# QuadF32.net
KiCad netlist of a schematic drawn in EAGLE
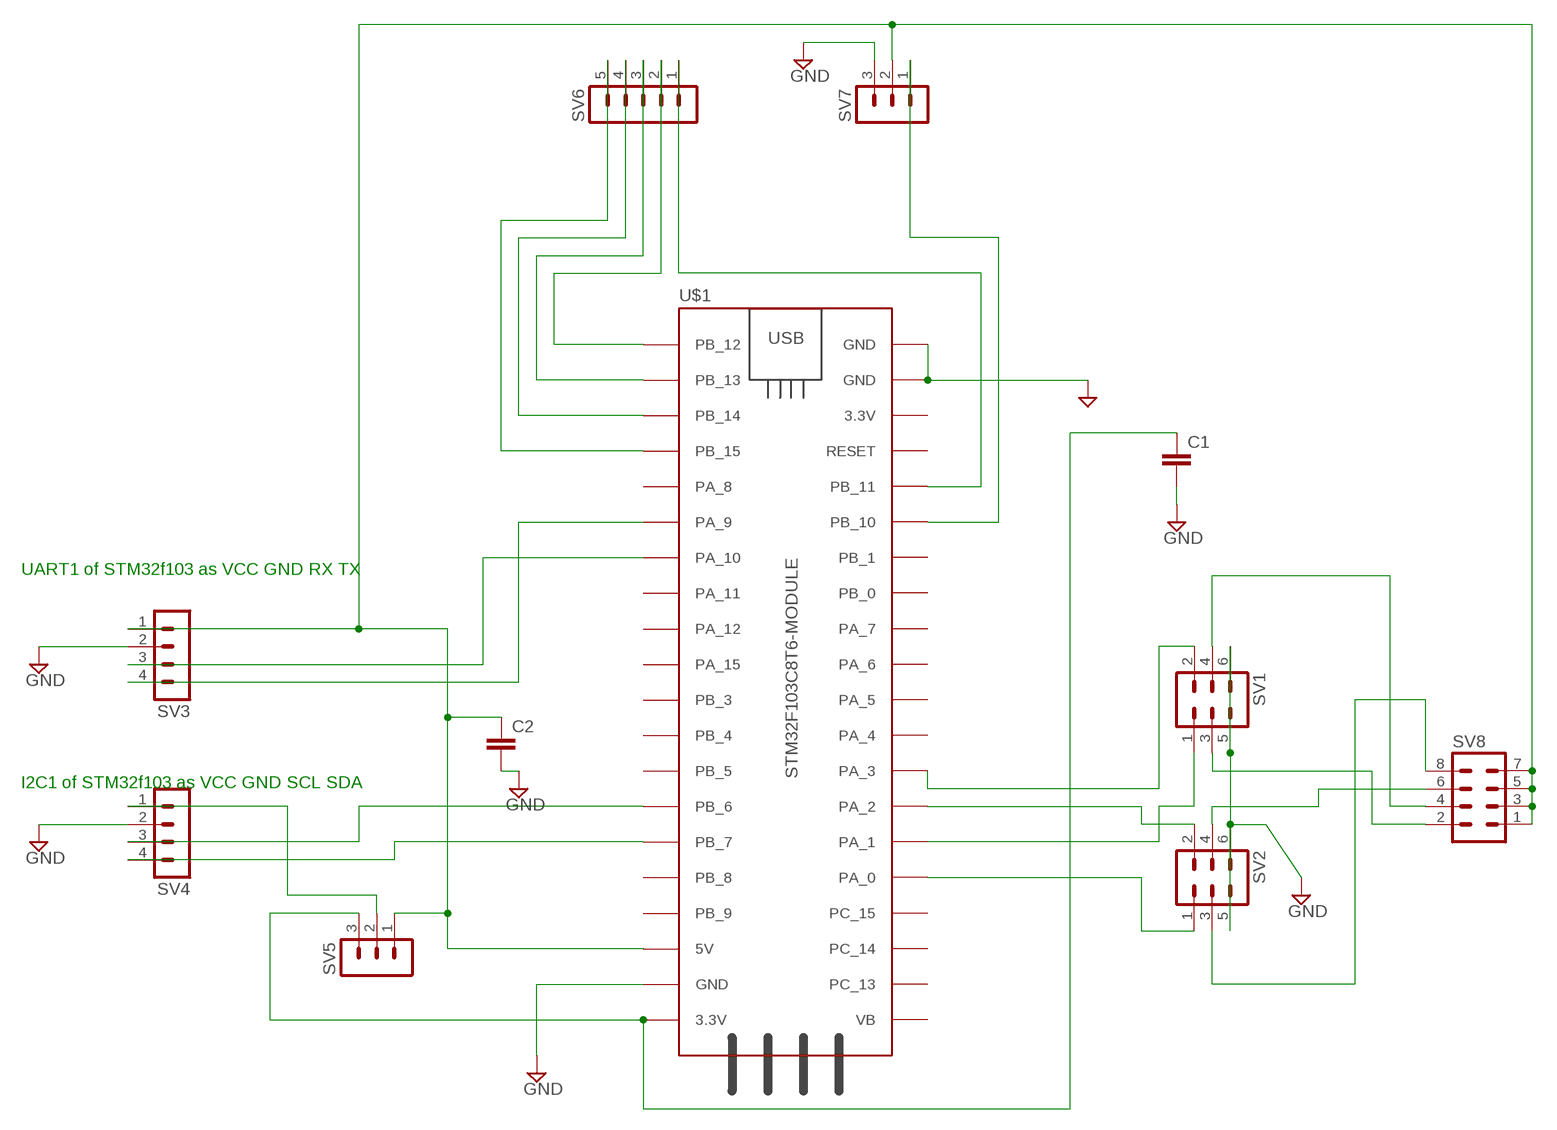
[diagram p0: schematic, sheet 1]

(export (version "E")
  (design (tool "Eeschema 10.0.6"))
  (components
    (comp (ref "C1")
      (value "C5/2.5")
      (footprint "eagle-import:C5B2.5")
      (libsource (lib "eagle-import") (part "C5/2.5"))
    )
    (comp (ref "C2")
      (value "C5/2.5")
      (footprint "eagle-import:C5B2.5")
      (libsource (lib "eagle-import") (part "C5/2.5"))
    )
    (comp (ref "SV1")
      (value "MA03-2")
      (footprint "eagle-import:MA03-2")
      (libsource (lib "eagle-import") (part "MA03-2"))
    )
    (comp (ref "SV2")
      (value "MA03-2")
      (footprint "eagle-import:MA03-2")
      (libsource (lib "eagle-import") (part "MA03-2"))
    )
    (comp (ref "SV3")
      (value "MA04-1")
      (footprint "eagle-import:MA04-1")
      (libsource (lib "eagle-import") (part "MA04-1"))
    )
    (comp (ref "SV4")
      (value "MA04-1")
      (footprint "eagle-import:MA04-1")
      (libsource (lib "eagle-import") (part "MA04-1"))
    )
    (comp (ref "SV5")
      (value "MA03-1")
      (footprint "eagle-import:MA03-1")
      (libsource (lib "eagle-import") (part "MA03-1"))
    )
    (comp (ref "SV6")
      (value "MA05-1")
      (footprint "eagle-import:MA05-1")
      (libsource (lib "eagle-import") (part "MA05-1"))
    )
    (comp (ref "SV7")
      (value "MA03-1")
      (footprint "eagle-import:MA03-1")
      (libsource (lib "eagle-import") (part "MA03-1"))
    )
    (comp (ref "SV8")
      (value "MA04-2")
      (footprint "eagle-import:MA04-2")
      (libsource (lib "eagle-import") (part "MA04-2"))
    )
    (comp (ref "U$1")
      (value "STM32F103C8T6-MODULE")
      (footprint "eagle-import:STM32F103C8T6-MODULE")
      (libsource (lib "eagle-import") (part "STM32F103C8T6-MODULE"))
    )
  )
  (nets
    (net (code "1") (name "GND") (class "Default")
      (node (ref "C1") (pin "2") (pinfunction "2_2") (pintype "passive"))
      (node (ref "C2") (pin "2") (pinfunction "2_2") (pintype "passive"))
      (node (ref "SV1") (pin "5") (pinfunction "5_5") (pintype "passive"))
      (node (ref "SV1") (pin "6") (pinfunction "6_6") (pintype "passive"))
      (node (ref "SV2") (pin "5") (pinfunction "5_5") (pintype "passive"))
      (node (ref "SV2") (pin "6") (pinfunction "6_6") (pintype "passive"))
      (node (ref "SV3") (pin "2") (pinfunction "2_2") (pintype "passive"))
      (node (ref "SV4") (pin "2") (pinfunction "2_2") (pintype "passive"))
      (node (ref "SV7") (pin "3") (pinfunction "3_3") (pintype "passive"))
      (node (ref "U$1") (pin "GND_1") (pinfunction "GND_GND_1") (pintype "bidirectional"))
      (node (ref "U$1") (pin "GND_2") (pinfunction "GND_GND_2") (pintype "bidirectional"))
      (node (ref "U$1") (pin "GND_3") (pinfunction "GND_GND_3") (pintype "power_in"))
    )
    (net (code "2") (name "Net-(C1-Pad1)") (class "Default")
      (node (ref "C1") (pin "1") (pinfunction "1_1") (pintype "passive"))
      (node (ref "SV5") (pin "3") (pinfunction "3_3") (pintype "passive"))
      (node (ref "U$1") (pin "3.3V_1") (pinfunction "3.3V_3.3V_1") (pintype "bidirectional"))
    )
    (net (code "3") (name "Net-(C2-Pad1)") (class "Default")
      (node (ref "C2") (pin "1") (pinfunction "1_1") (pintype "passive"))
      (node (ref "SV3") (pin "1") (pinfunction "1_1") (pintype "passive"))
      (node (ref "SV5") (pin "1") (pinfunction "1_1") (pintype "passive"))
      (node (ref "SV7") (pin "2") (pinfunction "2_2") (pintype "passive"))
      (node (ref "SV8") (pin "1") (pinfunction "1_1") (pintype "passive"))
      (node (ref "SV8") (pin "3") (pinfunction "3_3") (pintype "passive"))
      (node (ref "SV8") (pin "5") (pinfunction "5_5") (pintype "passive"))
      (node (ref "SV8") (pin "7") (pinfunction "7_7") (pintype "passive"))
      (node (ref "U$1") (pin "5V") (pinfunction "5V_5V") (pintype "bidirectional"))
    )
    (net (code "4") (name "Net-(SV1-Pad1)") (class "Default")
      (node (ref "SV1") (pin "1") (pinfunction "1_1") (pintype "passive"))
      (node (ref "U$1") (pin "PA_1") (pinfunction "PA_1_PA_1") (pintype "bidirectional"))
    )
    (net (code "5") (name "Net-(SV1-Pad2)") (class "Default")
      (node (ref "SV1") (pin "2") (pinfunction "2_2") (pintype "passive"))
      (node (ref "U$1") (pin "PA_3") (pinfunction "PA_3_PA_3") (pintype "bidirectional"))
    )
    (net (code "6") (name "Net-(SV1-Pad3)") (class "Default")
      (node (ref "SV1") (pin "3") (pinfunction "3_3") (pintype "passive"))
      (node (ref "SV8") (pin "2") (pinfunction "2_2") (pintype "passive"))
    )
    (net (code "7") (name "Net-(SV1-Pad4)") (class "Default")
      (node (ref "SV1") (pin "4") (pinfunction "4_4") (pintype "passive"))
      (node (ref "SV8") (pin "4") (pinfunction "4_4") (pintype "passive"))
    )
    (net (code "8") (name "Net-(SV2-Pad1)") (class "Default")
      (node (ref "SV2") (pin "1") (pinfunction "1_1") (pintype "passive"))
      (node (ref "U$1") (pin "PA_0") (pinfunction "PA_0_PA_0") (pintype "bidirectional"))
    )
    (net (code "9") (name "Net-(SV2-Pad2)") (class "Default")
      (node (ref "SV2") (pin "2") (pinfunction "2_2") (pintype "passive"))
      (node (ref "U$1") (pin "PA_2") (pinfunction "PA_2_PA_2") (pintype "bidirectional"))
    )
    (net (code "10") (name "Net-(SV2-Pad3)") (class "Default")
      (node (ref "SV2") (pin "3") (pinfunction "3_3") (pintype "passive"))
      (node (ref "SV8") (pin "8") (pinfunction "8_8") (pintype "passive"))
    )
    (net (code "11") (name "Net-(SV2-Pad4)") (class "Default")
      (node (ref "SV2") (pin "4") (pinfunction "4_4") (pintype "passive"))
      (node (ref "SV8") (pin "6") (pinfunction "6_6") (pintype "passive"))
    )
    (net (code "12") (name "Net-(SV3-Pad3)") (class "Default")
      (node (ref "SV3") (pin "3") (pinfunction "3_3") (pintype "passive"))
      (node (ref "U$1") (pin "PA_10") (pinfunction "PA_10_PA_10") (pintype "bidirectional"))
    )
    (net (code "13") (name "Net-(SV3-Pad4)") (class "Default")
      (node (ref "SV3") (pin "4") (pinfunction "4_4") (pintype "passive"))
      (node (ref "U$1") (pin "PA_9") (pinfunction "PA_9_PA_9") (pintype "bidirectional"))
    )
    (net (code "14") (name "Net-(SV4-Pad1)") (class "Default")
      (node (ref "SV4") (pin "1") (pinfunction "1_1") (pintype "passive"))
      (node (ref "SV5") (pin "2") (pinfunction "2_2") (pintype "passive"))
    )
    (net (code "15") (name "Net-(SV4-Pad3)") (class "Default")
      (node (ref "SV4") (pin "3") (pinfunction "3_3") (pintype "passive"))
      (node (ref "U$1") (pin "PB_6") (pinfunction "PB_6_PB_6") (pintype "bidirectional"))
    )
    (net (code "16") (name "Net-(SV4-Pad4)") (class "Default")
      (node (ref "SV4") (pin "4") (pinfunction "4_4") (pintype "passive"))
      (node (ref "U$1") (pin "PB_7") (pinfunction "PB_7_PB_7") (pintype "bidirectional"))
    )
    (net (code "17") (name "Net-(SV6-Pad1)") (class "Default")
      (node (ref "SV6") (pin "1") (pinfunction "1_1") (pintype "passive"))
      (node (ref "U$1") (pin "PB_11") (pinfunction "PB_11_PB_11") (pintype "bidirectional"))
    )
    (net (code "18") (name "Net-(SV6-Pad2)") (class "Default")
      (node (ref "SV6") (pin "2") (pinfunction "2_2") (pintype "passive"))
      (node (ref "U$1") (pin "PB_12") (pinfunction "PB_12_PB_12") (pintype "bidirectional"))
    )
    (net (code "19") (name "Net-(SV6-Pad3)") (class "Default")
      (node (ref "SV6") (pin "3") (pinfunction "3_3") (pintype "passive"))
      (node (ref "U$1") (pin "PB_13") (pinfunction "PB_13_PB_13") (pintype "bidirectional"))
    )
    (net (code "20") (name "Net-(SV6-Pad4)") (class "Default")
      (node (ref "SV6") (pin "4") (pinfunction "4_4") (pintype "passive"))
      (node (ref "U$1") (pin "PB_14") (pinfunction "PB_14_PB_14") (pintype "bidirectional"))
    )
    (net (code "21") (name "Net-(SV6-Pad5)") (class "Default")
      (node (ref "SV6") (pin "5") (pinfunction "5_5") (pintype "passive"))
      (node (ref "U$1") (pin "PB_15") (pinfunction "PB_15_PB_15") (pintype "bidirectional"))
    )
    (net (code "22") (name "Net-(SV7-Pad1)") (class "Default")
      (node (ref "SV7") (pin "1") (pinfunction "1_1") (pintype "passive"))
      (node (ref "U$1") (pin "PB_10") (pinfunction "PB_10_PB_10") (pintype "bidirectional"))
    )
    (net (code "23") (name "unconnected-(U$1-3.3V-Pad3.3V_2)") (class "Default")
      (node (ref "U$1") (pin "3.3V_2") (pinfunction "3.3V_3.3V_2") (pintype "bidirectional"))
    )
    (net (code "24") (name "unconnected-(U$1-PadPA_4)") (class "Default")
      (node (ref "U$1") (pin "PA_4") (pinfunction "PA_4_PA_4") (pintype "bidirectional"))
    )
    (net (code "25") (name "unconnected-(U$1-PadPA_5)") (class "Default")
      (node (ref "U$1") (pin "PA_5") (pinfunction "PA_5_PA_5") (pintype "bidirectional"))
    )
    (net (code "26") (name "unconnected-(U$1-PadPA_6)") (class "Default")
      (node (ref "U$1") (pin "PA_6") (pinfunction "PA_6_PA_6") (pintype "bidirectional"))
    )
    (net (code "27") (name "unconnected-(U$1-PadPA_7)") (class "Default")
      (node (ref "U$1") (pin "PA_7") (pinfunction "PA_7_PA_7") (pintype "bidirectional"))
    )
    (net (code "28") (name "unconnected-(U$1-PadPA_8)") (class "Default")
      (node (ref "U$1") (pin "PA_8") (pinfunction "PA_8_PA_8") (pintype "bidirectional"))
    )
    (net (code "29") (name "unconnected-(U$1-PadPA_11)") (class "Default")
      (node (ref "U$1") (pin "PA_11") (pinfunction "PA_11_PA_11") (pintype "bidirectional"))
    )
    (net (code "30") (name "unconnected-(U$1-PadPA_12)") (class "Default")
      (node (ref "U$1") (pin "PA_12") (pinfunction "PA_12_PA_12") (pintype "bidirectional"))
    )
    (net (code "31") (name "unconnected-(U$1-PadPA_15)") (class "Default")
      (node (ref "U$1") (pin "PA_15") (pinfunction "PA_15_PA_15") (pintype "bidirectional"))
    )
    (net (code "32") (name "unconnected-(U$1-PadPB_0)") (class "Default")
      (node (ref "U$1") (pin "PB_0") (pinfunction "PB_0_PB_0") (pintype "bidirectional"))
    )
    (net (code "33") (name "unconnected-(U$1-PadPB_1)") (class "Default")
      (node (ref "U$1") (pin "PB_1") (pinfunction "PB_1_PB_1") (pintype "bidirectional"))
    )
    (net (code "34") (name "unconnected-(U$1-PadPB_3)") (class "Default")
      (node (ref "U$1") (pin "PB_3") (pinfunction "PB_3_PB_3") (pintype "bidirectional"))
    )
    (net (code "35") (name "unconnected-(U$1-PadPB_4)") (class "Default")
      (node (ref "U$1") (pin "PB_4") (pinfunction "PB_4_PB_4") (pintype "bidirectional"))
    )
    (net (code "36") (name "unconnected-(U$1-PadPB_5)") (class "Default")
      (node (ref "U$1") (pin "PB_5") (pinfunction "PB_5_PB_5") (pintype "bidirectional"))
    )
    (net (code "37") (name "unconnected-(U$1-PadPB_8)") (class "Default")
      (node (ref "U$1") (pin "PB_8") (pinfunction "PB_8_PB_8") (pintype "bidirectional"))
    )
    (net (code "38") (name "unconnected-(U$1-PadPB_9)") (class "Default")
      (node (ref "U$1") (pin "PB_9") (pinfunction "PB_9_PB_9") (pintype "bidirectional"))
    )
    (net (code "39") (name "unconnected-(U$1-PadPC_13)") (class "Default")
      (node (ref "U$1") (pin "PC_13") (pinfunction "PC_13_PC_13") (pintype "bidirectional"))
    )
    (net (code "40") (name "unconnected-(U$1-PadPC_14)") (class "Default")
      (node (ref "U$1") (pin "PC_14") (pinfunction "PC_14_PC_14") (pintype "bidirectional"))
    )
    (net (code "41") (name "unconnected-(U$1-PadPC_15)") (class "Default")
      (node (ref "U$1") (pin "PC_15") (pinfunction "PC_15_PC_15") (pintype "bidirectional"))
    )
    (net (code "42") (name "unconnected-(U$1-PadRESET)") (class "Default")
      (node (ref "U$1") (pin "RESET") (pinfunction "RESET_RESET") (pintype "bidirectional"))
    )
    (net (code "43") (name "unconnected-(U$1-PadVB)") (class "Default")
      (node (ref "U$1") (pin "VB") (pinfunction "VB_VB") (pintype "bidirectional"))
    )
  )
)
